# TRANSLATOR_I2C.net
KiCad netlist of a schematic drawn in Altium Designer
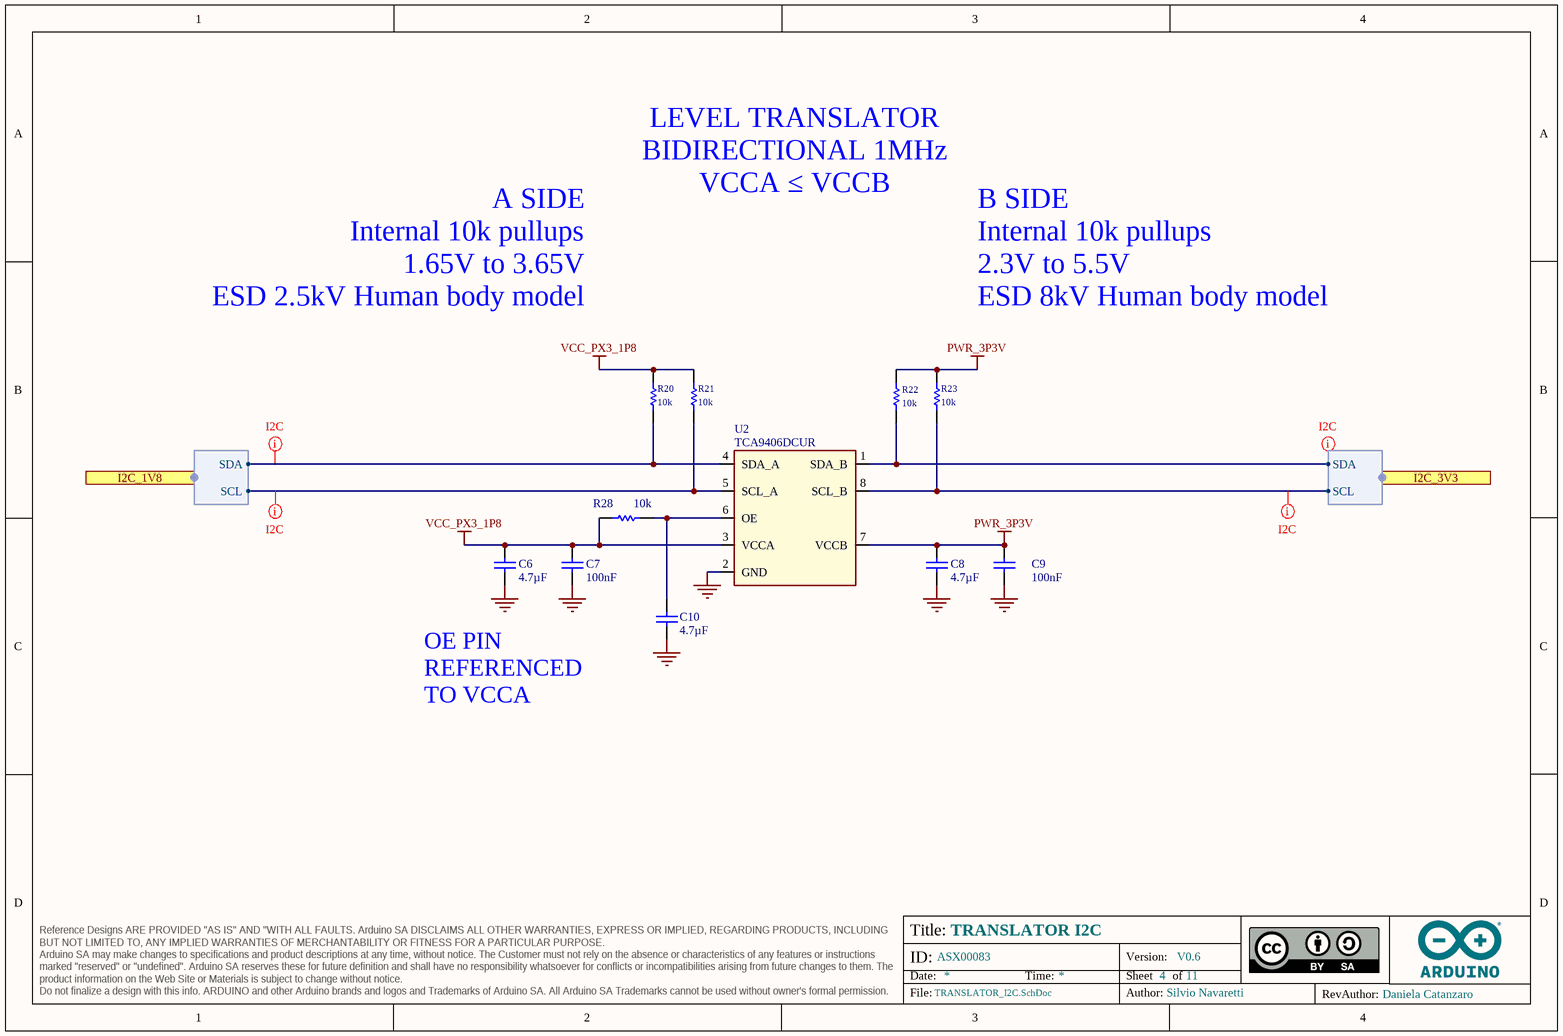
[diagram p0: TRANSLATOR_I2C.SchDoc]

(export (version "E")
  (design (tool "Eeschema 10.0.6"))
  (components
    (comp (ref "C6")
      (value "4.7µF")
      (footprint "CAP-0402")
      (description "CAP CHIP 0402 4.7uF 20% 6V3 X5R")
      (fields (field (name "MANUFACTURER") "Hottech") (field (name "PART NUMBER") "C1005A475M6R3NT"))
      (libsource (lib "Clean") (part "CAP"))
    )
    (comp (ref "C7")
      (value "100nF")
      (footprint "CAP-0402")
      (description "CAP CHIP 0402 100nF 10% 50V X5R")
      (fields (field (name "MANUFACTURER") "Murata") (field (name "PART NUMBER") "GRM155R61H104KE19D"))
      (libsource (lib "Clean") (part "CAP"))
    )
    (comp (ref "C8")
      (value "4.7µF")
      (footprint "CAP-0402")
      (description "CAP CHIP 0402 4.7uF 20% 6V3 X5R")
      (fields (field (name "MANUFACTURER") "Hottech") (field (name "PART NUMBER") "C1005A475M6R3NT"))
      (libsource (lib "Clean") (part "CAP"))
    )
    (comp (ref "C9")
      (value "100nF")
      (footprint "CAP-0402")
      (description "CAP CHIP 0402 100nF 10% 50V X5R")
      (fields (field (name "MANUFACTURER") "Murata") (field (name "PART NUMBER") "GRM155R61H104KE19D"))
      (libsource (lib "Clean") (part "CAP"))
    )
    (comp (ref "C10")
      (value "4.7µF")
      (footprint "CAP-0402")
      (description "CAP CHIP 0402 4.7uF 20% 6V3 X5R")
      (fields (field (name "MANUFACTURER") "Hottech") (field (name "PART NUMBER") "C1005A475M6R3NT"))
      (libsource (lib "Clean") (part "CAP"))
    )
    (comp (ref "R20")
      (value "10k")
      (footprint "RES-0402")
      (description "RES CHIP 0402 10k 1% 1/16W")
      (fields (field (name "PART NUMBER") "CRCW040210K0FKED") (field (name "MANUFACTURER") "Vishay"))
      (libsource (lib "Clean") (part "RES"))
    )
    (comp (ref "R21")
      (value "10k")
      (footprint "RES-0402")
      (description "RES CHIP 0402 10k 1% 1/16W")
      (fields (field (name "PART NUMBER") "CRCW040210K0FKED") (field (name "MANUFACTURER") "Vishay"))
      (libsource (lib "Clean") (part "RES"))
    )
    (comp (ref "R22")
      (value "10k")
      (footprint "RES-0402")
      (description "RES CHIP 0402 10k 1% 1/16W")
      (fields (field (name "PART NUMBER") "CRCW040210K0FKED") (field (name "MANUFACTURER") "Vishay"))
      (libsource (lib "Clean") (part "RES"))
    )
    (comp (ref "R23")
      (value "10k")
      (footprint "RES-0402")
      (description "RES CHIP 0402 10k 1% 1/16W")
      (fields (field (name "PART NUMBER") "CRCW040210K0FKED") (field (name "MANUFACTURER") "Vishay"))
      (libsource (lib "Clean") (part "RES"))
    )
    (comp (ref "R28")
      (value "10k")
      (footprint "RES-0402")
      (description "RES CHIP 0402 10k 1% 1/16W")
      (fields (field (name "PART NUMBER") "CRCW040210K0FKED") (field (name "MANUFACTURER") "Vishay"))
      (libsource (lib "Clean") (part "RES"))
    )
    (comp (ref "U2")
      (value "TCA9406DCUR")
      (footprint "VSSOP8 pitch 0.5mm body 3.1x2x0.9mm")
      (fields (field (name "MANUFACTURER") "Texas Instruments") (field (name "LCSC PART #") "C840107"))
      (libsource (lib "Clean") (part "TCA9406"))
    )
  )
  (nets
    (net (code "3") (name "GND") (class "Default")
      (node (ref "C10") (pin "1") (pinfunction "1_1") (pintype "passive"))
      (node (ref "C6") (pin "1") (pinfunction "1_1") (pintype "passive"))
      (node (ref "C7") (pin "2") (pinfunction "2_2") (pintype "passive"))
      (node (ref "C8") (pin "1") (pinfunction "1_1") (pintype "passive"))
      (node (ref "C9") (pin "2") (pinfunction "2_2") (pintype "passive"))
      (node (ref "U2") (pin "2") (pinfunction "GND_2") (pintype "passive"))
    )
    (net (code "4") (name "Net-(U2-OE)") (class "Default")
      (node (ref "C10") (pin "2") (pinfunction "2_2") (pintype "passive"))
      (node (ref "R28") (pin "1") (pinfunction "1_1") (pintype "passive"))
      (node (ref "U2") (pin "6") (pinfunction "OE_6") (pintype "passive"))
    )
    (net (code "5") (name "Net-(U2-SCL_A)") (class "Default")
      (node (ref "R21") (pin "1") (pinfunction "1_1") (pintype "passive"))
      (node (ref "U2") (pin "5") (pinfunction "SCL_A_5") (pintype "passive"))
    )
    (net (code "6") (name "Net-(U2-SCL_B)") (class "Default")
      (node (ref "R23") (pin "1") (pinfunction "1_1") (pintype "passive"))
      (node (ref "U2") (pin "8") (pinfunction "SCL_B_8") (pintype "passive"))
    )
    (net (code "7") (name "Net-(U2-SDA_A)") (class "Default")
      (node (ref "R20") (pin "1") (pinfunction "1_1") (pintype "passive"))
      (node (ref "U2") (pin "4") (pinfunction "SDA_A_4") (pintype "passive"))
    )
    (net (code "8") (name "Net-(U2-SDA_B)") (class "Default")
      (node (ref "R22") (pin "1") (pinfunction "1_1") (pintype "passive"))
      (node (ref "U2") (pin "1") (pinfunction "SDA_B_1") (pintype "passive"))
    )
    (net (code "9") (name "PWR_3P3V") (class "Default")
      (node (ref "C8") (pin "2") (pinfunction "2_2") (pintype "passive"))
      (node (ref "C9") (pin "1") (pinfunction "1_1") (pintype "passive"))
      (node (ref "R22") (pin "2") (pinfunction "2_2") (pintype "passive"))
      (node (ref "R23") (pin "2") (pinfunction "2_2") (pintype "passive"))
      (node (ref "U2") (pin "7") (pinfunction "VCCB_7") (pintype "passive"))
    )
    (net (code "10") (name "VCC_PX3_1P8") (class "Default")
      (node (ref "C6") (pin "2") (pinfunction "2_2") (pintype "passive"))
      (node (ref "C7") (pin "1") (pinfunction "1_1") (pintype "passive"))
      (node (ref "R20") (pin "2") (pinfunction "2_2") (pintype "passive"))
      (node (ref "R21") (pin "2") (pinfunction "2_2") (pintype "passive"))
      (node (ref "R28") (pin "2") (pinfunction "2_2") (pintype "passive"))
      (node (ref "U2") (pin "3") (pinfunction "VCCA_3") (pintype "passive"))
    )
  )
)
